# Aspen_Fever.net
KiCad netlist of a schematic drawn in EAGLE
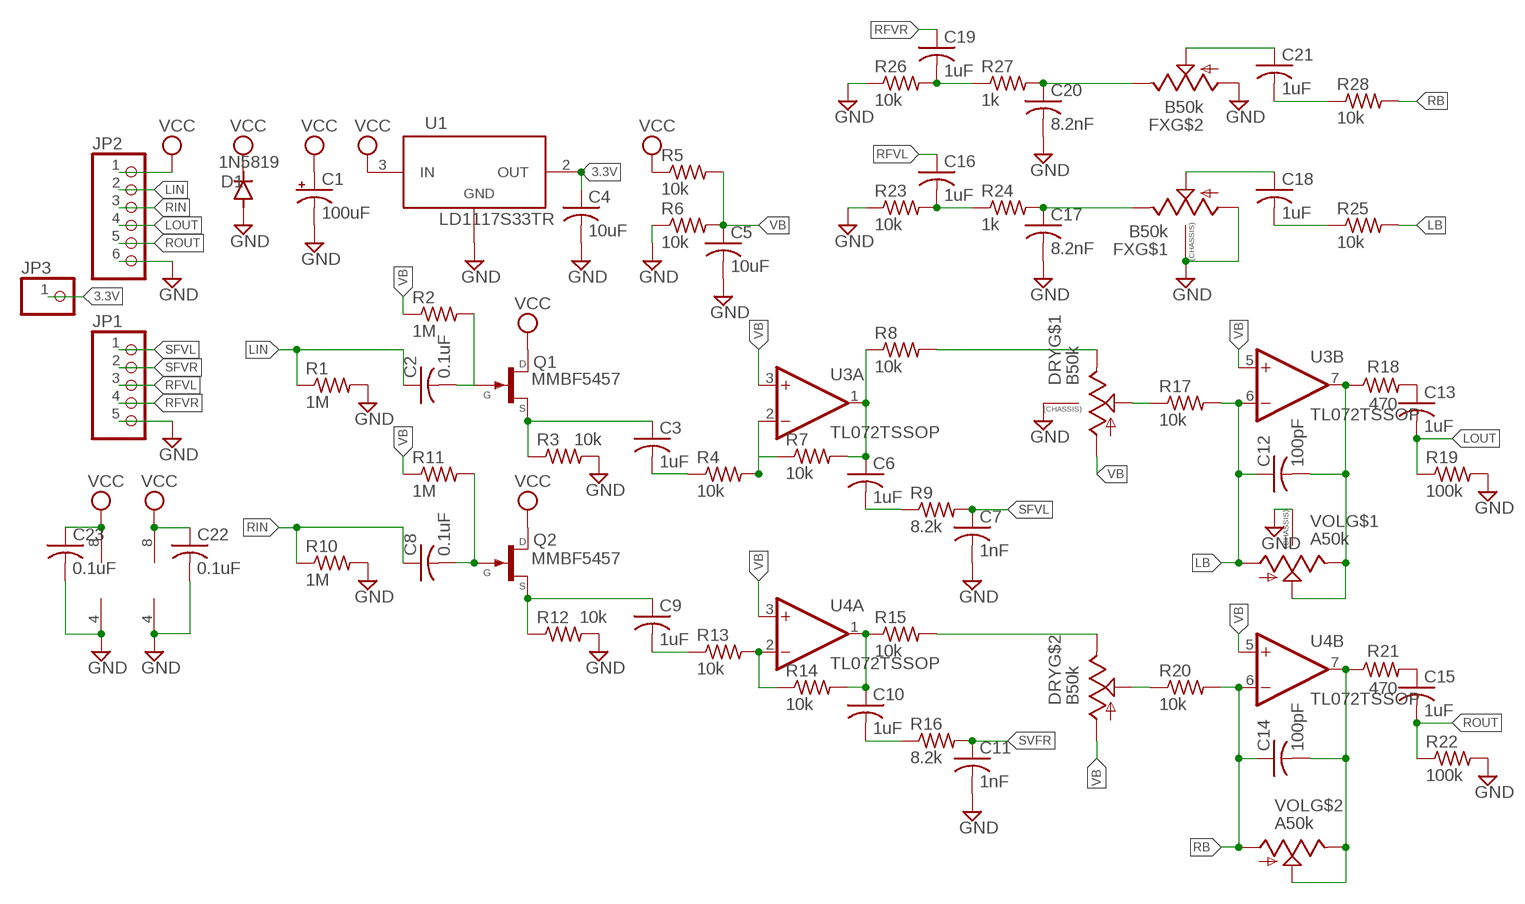
[diagram p0: schematic, sheet 1]

(export (version "E")
  (design (tool "Eeschema 10.0.6"))
  (components
    (comp (ref "C1")
      (value "100uF")
      (footprint "eagle-import:PAN_B_SMD+THRU")
      (libsource (lib "eagle-import") (part "CAP_SMD+THRUPAN_B"))
    )
    (comp (ref "C2")
      (value "0.1uF")
      (footprint "eagle-import:C0402")
      (libsource (lib "eagle-import") (part "C-USC0402"))
    )
    (comp (ref "C3")
      (value "1uF")
      (footprint "eagle-import:C0603")
      (libsource (lib "eagle-import") (part "adafruit_420_C-USC0603"))
    )
    (comp (ref "C4")
      (value "10uF")
      (footprint "eagle-import:C0805")
      (libsource (lib "eagle-import") (part "C-USC0805"))
    )
    (comp (ref "C5")
      (value "10uF")
      (footprint "eagle-import:C0805")
      (libsource (lib "eagle-import") (part "C-USC0805"))
    )
    (comp (ref "C6")
      (value "1uF")
      (footprint "eagle-import:C0603")
      (libsource (lib "eagle-import") (part "adafruit_420_C-USC0603"))
    )
    (comp (ref "C7")
      (value "1nF")
      (footprint "eagle-import:C0402")
      (libsource (lib "eagle-import") (part "C-USC0402"))
    )
    (comp (ref "C8")
      (value "0.1uF")
      (footprint "eagle-import:C0402")
      (libsource (lib "eagle-import") (part "C-USC0402"))
    )
    (comp (ref "C9")
      (value "1uF")
      (footprint "eagle-import:C0603")
      (libsource (lib "eagle-import") (part "adafruit_420_C-USC0603"))
    )
    (comp (ref "C10")
      (value "1uF")
      (footprint "eagle-import:C0603")
      (libsource (lib "eagle-import") (part "adafruit_420_C-USC0603"))
    )
    (comp (ref "C11")
      (value "1nF")
      (footprint "eagle-import:C0402")
      (libsource (lib "eagle-import") (part "C-USC0402"))
    )
    (comp (ref "C12")
      (value "100pF")
      (footprint "eagle-import:C0402")
      (libsource (lib "eagle-import") (part "C-USC0402"))
    )
    (comp (ref "C13")
      (value "1uF")
      (footprint "eagle-import:C0603")
      (libsource (lib "eagle-import") (part "adafruit_420_C-USC0603"))
    )
    (comp (ref "C14")
      (value "100pF")
      (footprint "eagle-import:C0402")
      (libsource (lib "eagle-import") (part "C-USC0402"))
    )
    (comp (ref "C15")
      (value "1uF")
      (footprint "eagle-import:C0603")
      (libsource (lib "eagle-import") (part "adafruit_420_C-USC0603"))
    )
    (comp (ref "C16")
      (value "1uF")
      (footprint "eagle-import:C0603")
      (libsource (lib "eagle-import") (part "adafruit_420_C-USC0603"))
    )
    (comp (ref "C17")
      (value "8.2nF")
      (footprint "eagle-import:C0402")
      (libsource (lib "eagle-import") (part "C-USC0402"))
    )
    (comp (ref "C18")
      (value "1uF")
      (footprint "eagle-import:C0603")
      (libsource (lib "eagle-import") (part "adafruit_420_C-USC0603"))
    )
    (comp (ref "C19")
      (value "1uF")
      (footprint "eagle-import:C0603")
      (libsource (lib "eagle-import") (part "adafruit_420_C-USC0603"))
    )
    (comp (ref "C20")
      (value "8.2nF")
      (footprint "eagle-import:C0402")
      (libsource (lib "eagle-import") (part "C-USC0402"))
    )
    (comp (ref "C21")
      (value "1uF")
      (footprint "eagle-import:C0603")
      (libsource (lib "eagle-import") (part "adafruit_420_C-USC0603"))
    )
    (comp (ref "C22")
      (value "0.1uF")
      (footprint "eagle-import:C0402")
      (libsource (lib "eagle-import") (part "C-USC0402"))
    )
    (comp (ref "C23")
      (value "0.1uF")
      (footprint "eagle-import:C0402")
      (libsource (lib "eagle-import") (part "C-USC0402"))
    )
    (comp (ref "D1")
      (value "1N5819")
      (footprint "eagle-import:SOD123")
      (libsource (lib "eagle-import") (part "DIODE-SOD123"))
    )
    (comp (ref "DRY")
      (value "B50k")
      (footprint "eagle-import:DUAL_9MM_SNAP-IN_POT")
      (libsource (lib "eagle-import") (part "ALPHA-9MM-DUALPOT"))
    )
    (comp (ref "FX")
      (value "B50k")
      (footprint "eagle-import:DUAL_9MM_SNAP-IN_POT")
      (libsource (lib "eagle-import") (part "ALPHA-9MM-DUALPOT"))
    )
    (comp (ref "JP1")
      (value "PINHD-1X5")
      (footprint "eagle-import:1X05")
      (libsource (lib "eagle-import") (part "PINHD-1X5"))
    )
    (comp (ref "JP2")
      (value "PINHD-1X6")
      (footprint "eagle-import:1X06")
      (libsource (lib "eagle-import") (part "PINHD-1X6"))
    )
    (comp (ref "JP3")
      (value "PINHD-1X1")
      (footprint "eagle-import:1X01")
      (libsource (lib "eagle-import") (part "PINHD-1X1"))
    )
    (comp (ref "Q1")
      (value "MMBF5457")
      (footprint "eagle-import:SOT23")
      (fields (field (name "MF") "ON Semiconductor"))
      (libsource (lib "eagle-import") (part "MMBF5457"))
    )
    (comp (ref "Q2")
      (value "MMBF5457")
      (footprint "eagle-import:SOT23")
      (fields (field (name "MF") "ON Semiconductor"))
      (libsource (lib "eagle-import") (part "MMBF5457"))
    )
    (comp (ref "R1")
      (value "1M")
      (footprint "eagle-import:R0402")
      (libsource (lib "eagle-import") (part "R-US_R0402"))
    )
    (comp (ref "R2")
      (value "1M")
      (footprint "eagle-import:R0402")
      (libsource (lib "eagle-import") (part "R-US_R0402"))
    )
    (comp (ref "R3")
      (value "10k")
      (footprint "eagle-import:R0402")
      (libsource (lib "eagle-import") (part "R-US_R0402"))
    )
    (comp (ref "R4")
      (value "10k")
      (footprint "eagle-import:R0402")
      (libsource (lib "eagle-import") (part "R-US_R0402"))
    )
    (comp (ref "R5")
      (value "10k")
      (footprint "eagle-import:R0402")
      (libsource (lib "eagle-import") (part "R-US_R0402"))
    )
    (comp (ref "R6")
      (value "10k")
      (footprint "eagle-import:R0402")
      (libsource (lib "eagle-import") (part "R-US_R0402"))
    )
    (comp (ref "R7")
      (value "10k")
      (footprint "eagle-import:R0402")
      (libsource (lib "eagle-import") (part "R-US_R0402"))
    )
    (comp (ref "R8")
      (value "10k")
      (footprint "eagle-import:R0402")
      (libsource (lib "eagle-import") (part "R-US_R0402"))
    )
    (comp (ref "R9")
      (value "8.2k")
      (footprint "eagle-import:R0402")
      (libsource (lib "eagle-import") (part "R-US_R0402"))
    )
    (comp (ref "R10")
      (value "1M")
      (footprint "eagle-import:R0402")
      (libsource (lib "eagle-import") (part "R-US_R0402"))
    )
    (comp (ref "R11")
      (value "1M")
      (footprint "eagle-import:R0402")
      (libsource (lib "eagle-import") (part "R-US_R0402"))
    )
    (comp (ref "R12")
      (value "10k")
      (footprint "eagle-import:R0402")
      (libsource (lib "eagle-import") (part "R-US_R0402"))
    )
    (comp (ref "R13")
      (value "10k")
      (footprint "eagle-import:R0402")
      (libsource (lib "eagle-import") (part "R-US_R0402"))
    )
    (comp (ref "R14")
      (value "10k")
      (footprint "eagle-import:R0402")
      (libsource (lib "eagle-import") (part "R-US_R0402"))
    )
    (comp (ref "R15")
      (value "10k")
      (footprint "eagle-import:R0402")
      (libsource (lib "eagle-import") (part "R-US_R0402"))
    )
    (comp (ref "R16")
      (value "8.2k")
      (footprint "eagle-import:R0402")
      (libsource (lib "eagle-import") (part "R-US_R0402"))
    )
    (comp (ref "R17")
      (value "10k")
      (footprint "eagle-import:R0402")
      (libsource (lib "eagle-import") (part "R-US_R0402"))
    )
    (comp (ref "R18")
      (value "470")
      (footprint "eagle-import:R0402")
      (libsource (lib "eagle-import") (part "R-US_R0402"))
    )
    (comp (ref "R19")
      (value "100k")
      (footprint "eagle-import:R0402")
      (libsource (lib "eagle-import") (part "R-US_R0402"))
    )
    (comp (ref "R20")
      (value "10k")
      (footprint "eagle-import:R0402")
      (libsource (lib "eagle-import") (part "R-US_R0402"))
    )
    (comp (ref "R21")
      (value "470")
      (footprint "eagle-import:R0402")
      (libsource (lib "eagle-import") (part "R-US_R0402"))
    )
    (comp (ref "R22")
      (value "100k")
      (footprint "eagle-import:R0402")
      (libsource (lib "eagle-import") (part "R-US_R0402"))
    )
    (comp (ref "R23")
      (value "10k")
      (footprint "eagle-import:R0402")
      (libsource (lib "eagle-import") (part "R-US_R0402"))
    )
    (comp (ref "R24")
      (value "1k")
      (footprint "eagle-import:R0402")
      (libsource (lib "eagle-import") (part "R-US_R0402"))
    )
    (comp (ref "R25")
      (value "10k")
      (footprint "eagle-import:R0402")
      (libsource (lib "eagle-import") (part "R-US_R0402"))
    )
    (comp (ref "R26")
      (value "10k")
      (footprint "eagle-import:R0402")
      (libsource (lib "eagle-import") (part "R-US_R0402"))
    )
    (comp (ref "R27")
      (value "1k")
      (footprint "eagle-import:R0402")
      (libsource (lib "eagle-import") (part "R-US_R0402"))
    )
    (comp (ref "R28")
      (value "10k")
      (footprint "eagle-import:R0402")
      (libsource (lib "eagle-import") (part "R-US_R0402"))
    )
    (comp (ref "U1")
      (value "LD1117S33TR")
      (footprint "eagle-import:SOT-223")
      (fields
        (field (name "DIGIKEY_PART_NUMBER") "497-1242-2-ND")
        (field (name "MANUFACTURER") "STMicroelectronics")
        (field (name "CREATED_BY") "PCBLayout.com")
      )
      (libsource (lib "eagle-import") (part "LD1117S33TR"))
    )
    (comp (ref "U3")
      (value "TL072TSSOP")
      (footprint "eagle-import:TSSOP-8")
      (libsource (lib "eagle-import") (part "TL072TSSOP"))
    )
    (comp (ref "U4")
      (value "TL072TSSOP")
      (footprint "eagle-import:TSSOP-8")
      (libsource (lib "eagle-import") (part "TL072TSSOP"))
    )
    (comp (ref "VOL")
      (value "A50k")
      (footprint "eagle-import:DUAL_9MM_SNAP-IN_POT")
      (libsource (lib "eagle-import") (part "ALPHA-9MM-DUALPOT"))
    )
  )
  (nets
    (net (code "1") (name "3.3V") (class "Default")
      (node (ref "C4") (pin "1") (pinfunction "1_1") (pintype "passive"))
      (node (ref "JP3") (pin "1") (pinfunction "1_1") (pintype "passive"))
      (node (ref "U1") (pin "2") (pinfunction "OUT_2") (pintype "output"))
      (node (ref "U1") (pin "4") (pinfunction "4_4") (pintype "passive"))
    )
    (net (code "2") (name "GND") (class "Default")
      (node (ref "C1") (pin "-") (pinfunction "-_-") (pintype "passive"))
      (node (ref "C1") (pin "--") (pinfunction "-_--") (pintype "passive"))
      (node (ref "C11") (pin "2") (pinfunction "2_2") (pintype "passive"))
      (node (ref "C17") (pin "2") (pinfunction "2_2") (pintype "passive"))
      (node (ref "C20") (pin "2") (pinfunction "2_2") (pintype "passive"))
      (node (ref "C22") (pin "2") (pinfunction "2_2") (pintype "passive"))
      (node (ref "C23") (pin "2") (pinfunction "2_2") (pintype "passive"))
      (node (ref "C4") (pin "2") (pinfunction "2_2") (pintype "passive"))
      (node (ref "C5") (pin "2") (pinfunction "2_2") (pintype "passive"))
      (node (ref "C7") (pin "2") (pinfunction "2_2") (pintype "passive"))
      (node (ref "D1") (pin "A") (pinfunction "A_A") (pintype "passive"))
      (node (ref "DRY") (pin "CHASSIS1") (pinfunction "P$1_CHASSIS1") (pintype "passive"))
      (node (ref "DRY") (pin "CHASSIS2") (pinfunction "P$1_CHASSIS2") (pintype "passive"))
      (node (ref "FX") (pin "1") (pinfunction "A_1") (pintype "passive"))
      (node (ref "FX") (pin "1B") (pinfunction "A_1B") (pintype "passive"))
      (node (ref "FX") (pin "CHASSIS1") (pinfunction "P$1_CHASSIS1") (pintype "passive"))
      (node (ref "FX") (pin "CHASSIS2") (pinfunction "P$1_CHASSIS2") (pintype "passive"))
      (node (ref "JP1") (pin "5") (pinfunction "5_5") (pintype "passive"))
      (node (ref "JP2") (pin "6") (pinfunction "6_6") (pintype "passive"))
      (node (ref "R1") (pin "2") (pinfunction "2_2") (pintype "passive"))
      (node (ref "R10") (pin "2") (pinfunction "2_2") (pintype "passive"))
      (node (ref "R12") (pin "2") (pinfunction "2_2") (pintype "passive"))
      (node (ref "R19") (pin "2") (pinfunction "2_2") (pintype "passive"))
      (node (ref "R22") (pin "2") (pinfunction "2_2") (pintype "passive"))
      (node (ref "R23") (pin "1") (pinfunction "1_1") (pintype "passive"))
      (node (ref "R26") (pin "1") (pinfunction "1_1") (pintype "passive"))
      (node (ref "R3") (pin "2") (pinfunction "2_2") (pintype "passive"))
      (node (ref "R6") (pin "1") (pinfunction "1_1") (pintype "passive"))
      (node (ref "U1") (pin "1") (pinfunction "ADJ/GND_1") (pintype "power_in"))
      (node (ref "U3") (pin "4") (pinfunction "V-_4") (pintype "power_in"))
      (node (ref "U4") (pin "4") (pinfunction "V-_4") (pintype "power_in"))
      (node (ref "VOL") (pin "CHASSIS1") (pinfunction "P$1_CHASSIS1") (pintype "passive"))
      (node (ref "VOL") (pin "CHASSIS2") (pinfunction "P$1_CHASSIS2") (pintype "passive"))
    )
    (net (code "3") (name "LB") (class "Default")
      (node (ref "C12") (pin "1") (pinfunction "1_1") (pintype "passive"))
      (node (ref "R17") (pin "2") (pinfunction "2_2") (pintype "passive"))
      (node (ref "R25") (pin "2") (pinfunction "2_2") (pintype "passive"))
      (node (ref "U3") (pin "6") (pinfunction "-IN_6") (pintype "input"))
      (node (ref "VOL") (pin "1") (pinfunction "A_1") (pintype "passive"))
    )
    (net (code "4") (name "LIN") (class "Default")
      (node (ref "C2") (pin "1") (pinfunction "1_1") (pintype "passive"))
      (node (ref "JP2") (pin "2") (pinfunction "2_2") (pintype "passive"))
      (node (ref "R1") (pin "1") (pinfunction "1_1") (pintype "passive"))
    )
    (net (code "5") (name "LOUT") (class "Default")
      (node (ref "C13") (pin "2") (pinfunction "2_2") (pintype "passive"))
      (node (ref "JP2") (pin "4") (pinfunction "4_4") (pintype "passive"))
      (node (ref "R19") (pin "1") (pinfunction "1_1") (pintype "passive"))
    )
    (net (code "6") (name "Net-(C3-Pad2)") (class "Default")
      (node (ref "C3") (pin "2") (pinfunction "2_2") (pintype "passive"))
      (node (ref "R4") (pin "1") (pinfunction "1_1") (pintype "passive"))
    )
    (net (code "7") (name "Net-(C6-Pad2)") (class "Default")
      (node (ref "C6") (pin "2") (pinfunction "2_2") (pintype "passive"))
      (node (ref "R9") (pin "1") (pinfunction "1_1") (pintype "passive"))
    )
    (net (code "8") (name "Net-(C9-Pad2)") (class "Default")
      (node (ref "C9") (pin "2") (pinfunction "2_2") (pintype "passive"))
      (node (ref "R13") (pin "1") (pinfunction "1_1") (pintype "passive"))
    )
    (net (code "9") (name "Net-(C10-Pad2)") (class "Default")
      (node (ref "C10") (pin "2") (pinfunction "2_2") (pintype "passive"))
      (node (ref "R16") (pin "1") (pinfunction "1_1") (pintype "passive"))
    )
    (net (code "10") (name "Net-(C13-Pad1)") (class "Default")
      (node (ref "C13") (pin "1") (pinfunction "1_1") (pintype "passive"))
      (node (ref "R18") (pin "2") (pinfunction "2_2") (pintype "passive"))
    )
    (net (code "11") (name "Net-(C15-Pad1)") (class "Default")
      (node (ref "C15") (pin "1") (pinfunction "1_1") (pintype "passive"))
      (node (ref "R21") (pin "2") (pinfunction "2_2") (pintype "passive"))
    )
    (net (code "12") (name "Net-(C16-Pad2)") (class "Default")
      (node (ref "C16") (pin "2") (pinfunction "2_2") (pintype "passive"))
      (node (ref "R23") (pin "2") (pinfunction "2_2") (pintype "passive"))
      (node (ref "R24") (pin "1") (pinfunction "1_1") (pintype "passive"))
    )
    (net (code "13") (name "Net-(C18-Pad2)") (class "Default")
      (node (ref "C18") (pin "2") (pinfunction "2_2") (pintype "passive"))
      (node (ref "R25") (pin "1") (pinfunction "1_1") (pintype "passive"))
    )
    (net (code "14") (name "Net-(C19-Pad2)") (class "Default")
      (node (ref "C19") (pin "2") (pinfunction "2_2") (pintype "passive"))
      (node (ref "R26") (pin "2") (pinfunction "2_2") (pintype "passive"))
      (node (ref "R27") (pin "1") (pinfunction "1_1") (pintype "passive"))
    )
    (net (code "15") (name "Net-(C21-Pad2)") (class "Default")
      (node (ref "C21") (pin "2") (pinfunction "2_2") (pintype "passive"))
      (node (ref "R28") (pin "1") (pinfunction "1_1") (pintype "passive"))
    )
    (net (code "16") (name "Net-(DRYA-E)") (class "Default")
      (node (ref "DRY") (pin "3") (pinfunction "E_3") (pintype "passive"))
      (node (ref "R8") (pin "2") (pinfunction "2_2") (pintype "passive"))
    )
    (net (code "17") (name "Net-(DRYA-S)") (class "Default")
      (node (ref "DRY") (pin "2") (pinfunction "S_2") (pintype "passive"))
      (node (ref "R17") (pin "1") (pinfunction "1_1") (pintype "passive"))
    )
    (net (code "18") (name "Net-(DRYB-E)") (class "Default")
      (node (ref "DRY") (pin "3B") (pinfunction "E_3B") (pintype "passive"))
      (node (ref "R15") (pin "2") (pinfunction "2_2") (pintype "passive"))
    )
    (net (code "19") (name "Net-(DRYB-S)") (class "Default")
      (node (ref "DRY") (pin "2B") (pinfunction "S_2B") (pintype "passive"))
      (node (ref "R20") (pin "1") (pinfunction "1_1") (pintype "passive"))
    )
    (net (code "20") (name "Net-(FXA-E)") (class "Default")
      (node (ref "C17") (pin "1") (pinfunction "1_1") (pintype "passive"))
      (node (ref "FX") (pin "3") (pinfunction "E_3") (pintype "passive"))
      (node (ref "R24") (pin "2") (pinfunction "2_2") (pintype "passive"))
    )
    (net (code "21") (name "Net-(FXA-S)") (class "Default")
      (node (ref "C18") (pin "1") (pinfunction "1_1") (pintype "passive"))
      (node (ref "FX") (pin "2") (pinfunction "S_2") (pintype "passive"))
    )
    (net (code "22") (name "Net-(FXB-E)") (class "Default")
      (node (ref "C20") (pin "1") (pinfunction "1_1") (pintype "passive"))
      (node (ref "FX") (pin "3B") (pinfunction "E_3B") (pintype "passive"))
      (node (ref "R27") (pin "2") (pinfunction "2_2") (pintype "passive"))
    )
    (net (code "23") (name "Net-(FXB-S)") (class "Default")
      (node (ref "C21") (pin "1") (pinfunction "1_1") (pintype "passive"))
      (node (ref "FX") (pin "2B") (pinfunction "S_2B") (pintype "passive"))
    )
    (net (code "24") (name "Net-(Q1-G)") (class "Default")
      (node (ref "C2") (pin "2") (pinfunction "2_2") (pintype "passive"))
      (node (ref "Q1") (pin "3") (pinfunction "G_3") (pintype "passive"))
      (node (ref "R2") (pin "2") (pinfunction "2_2") (pintype "passive"))
    )
    (net (code "25") (name "Net-(Q1-S)") (class "Default")
      (node (ref "C3") (pin "1") (pinfunction "1_1") (pintype "passive"))
      (node (ref "Q1") (pin "2") (pinfunction "S_2") (pintype "passive"))
      (node (ref "R3") (pin "1") (pinfunction "1_1") (pintype "passive"))
    )
    (net (code "26") (name "Net-(Q2-G)") (class "Default")
      (node (ref "C8") (pin "2") (pinfunction "2_2") (pintype "passive"))
      (node (ref "Q2") (pin "3") (pinfunction "G_3") (pintype "passive"))
      (node (ref "R11") (pin "2") (pinfunction "2_2") (pintype "passive"))
    )
    (net (code "27") (name "Net-(Q2-S)") (class "Default")
      (node (ref "C9") (pin "1") (pinfunction "1_1") (pintype "passive"))
      (node (ref "Q2") (pin "2") (pinfunction "S_2") (pintype "passive"))
      (node (ref "R12") (pin "1") (pinfunction "1_1") (pintype "passive"))
    )
    (net (code "28") (name "Net-(U3A--IN)") (class "Default")
      (node (ref "R4") (pin "2") (pinfunction "2_2") (pintype "passive"))
      (node (ref "R7") (pin "1") (pinfunction "1_1") (pintype "passive"))
      (node (ref "U3") (pin "2") (pinfunction "-IN_2") (pintype "input"))
    )
    (net (code "29") (name "Net-(U3A-OUT)") (class "Default")
      (node (ref "C6") (pin "1") (pinfunction "1_1") (pintype "passive"))
      (node (ref "R7") (pin "2") (pinfunction "2_2") (pintype "passive"))
      (node (ref "R8") (pin "1") (pinfunction "1_1") (pintype "passive"))
      (node (ref "U3") (pin "1") (pinfunction "OUT_1") (pintype "output"))
    )
    (net (code "30") (name "Net-(U3B-OUT)") (class "Default")
      (node (ref "C12") (pin "2") (pinfunction "2_2") (pintype "passive"))
      (node (ref "R18") (pin "1") (pinfunction "1_1") (pintype "passive"))
      (node (ref "U3") (pin "7") (pinfunction "OUT_7") (pintype "output"))
      (node (ref "VOL") (pin "2") (pinfunction "S_2") (pintype "passive"))
      (node (ref "VOL") (pin "3") (pinfunction "E_3") (pintype "passive"))
    )
    (net (code "31") (name "Net-(U4A--IN)") (class "Default")
      (node (ref "R13") (pin "2") (pinfunction "2_2") (pintype "passive"))
      (node (ref "R14") (pin "1") (pinfunction "1_1") (pintype "passive"))
      (node (ref "U4") (pin "2") (pinfunction "-IN_2") (pintype "input"))
    )
    (net (code "32") (name "Net-(U4A-OUT)") (class "Default")
      (node (ref "C10") (pin "1") (pinfunction "1_1") (pintype "passive"))
      (node (ref "R14") (pin "2") (pinfunction "2_2") (pintype "passive"))
      (node (ref "R15") (pin "1") (pinfunction "1_1") (pintype "passive"))
      (node (ref "U4") (pin "1") (pinfunction "OUT_1") (pintype "output"))
    )
    (net (code "33") (name "Net-(U4B-OUT)") (class "Default")
      (node (ref "C14") (pin "2") (pinfunction "2_2") (pintype "passive"))
      (node (ref "R21") (pin "1") (pinfunction "1_1") (pintype "passive"))
      (node (ref "U4") (pin "7") (pinfunction "OUT_7") (pintype "output"))
      (node (ref "VOL") (pin "2B") (pinfunction "S_2B") (pintype "passive"))
      (node (ref "VOL") (pin "3B") (pinfunction "E_3B") (pintype "passive"))
    )
    (net (code "34") (name "RB") (class "Default")
      (node (ref "C14") (pin "1") (pinfunction "1_1") (pintype "passive"))
      (node (ref "R20") (pin "2") (pinfunction "2_2") (pintype "passive"))
      (node (ref "R28") (pin "2") (pinfunction "2_2") (pintype "passive"))
      (node (ref "U4") (pin "6") (pinfunction "-IN_6") (pintype "input"))
      (node (ref "VOL") (pin "1B") (pinfunction "A_1B") (pintype "passive"))
    )
    (net (code "35") (name "RFVL") (class "Default")
      (node (ref "C16") (pin "1") (pinfunction "1_1") (pintype "passive"))
      (node (ref "JP1") (pin "3") (pinfunction "3_3") (pintype "passive"))
    )
    (net (code "36") (name "RFVR") (class "Default")
      (node (ref "C19") (pin "1") (pinfunction "1_1") (pintype "passive"))
      (node (ref "JP1") (pin "4") (pinfunction "4_4") (pintype "passive"))
    )
    (net (code "37") (name "RIN") (class "Default")
      (node (ref "C8") (pin "1") (pinfunction "1_1") (pintype "passive"))
      (node (ref "JP2") (pin "3") (pinfunction "3_3") (pintype "passive"))
      (node (ref "R10") (pin "1") (pinfunction "1_1") (pintype "passive"))
    )
    (net (code "38") (name "ROUT") (class "Default")
      (node (ref "C15") (pin "2") (pinfunction "2_2") (pintype "passive"))
      (node (ref "JP2") (pin "5") (pinfunction "5_5") (pintype "passive"))
      (node (ref "R22") (pin "1") (pinfunction "1_1") (pintype "passive"))
    )
    (net (code "39") (name "SFVL") (class "Default")
      (node (ref "C7") (pin "1") (pinfunction "1_1") (pintype "passive"))
      (node (ref "JP1") (pin "1") (pinfunction "1_1") (pintype "passive"))
      (node (ref "R9") (pin "2") (pinfunction "2_2") (pintype "passive"))
    )
    (net (code "40") (name "SFVR") (class "Default")
      (node (ref "JP1") (pin "2") (pinfunction "2_2") (pintype "passive"))
    )
    (net (code "41") (name "SVFR") (class "Default")
      (node (ref "C11") (pin "1") (pinfunction "1_1") (pintype "passive"))
      (node (ref "R16") (pin "2") (pinfunction "2_2") (pintype "passive"))
    )
    (net (code "42") (name "VB") (class "Default")
      (node (ref "C5") (pin "1") (pinfunction "1_1") (pintype "passive"))
      (node (ref "DRY") (pin "1") (pinfunction "A_1") (pintype "passive"))
      (node (ref "DRY") (pin "1B") (pinfunction "A_1B") (pintype "passive"))
      (node (ref "R11") (pin "1") (pinfunction "1_1") (pintype "passive"))
      (node (ref "R2") (pin "1") (pinfunction "1_1") (pintype "passive"))
      (node (ref "R5") (pin "2") (pinfunction "2_2") (pintype "passive"))
      (node (ref "R6") (pin "2") (pinfunction "2_2") (pintype "passive"))
      (node (ref "U3") (pin "3") (pinfunction "+IN_3") (pintype "input"))
      (node (ref "U3") (pin "5") (pinfunction "+IN_5") (pintype "input"))
      (node (ref "U4") (pin "3") (pinfunction "+IN_3") (pintype "input"))
      (node (ref "U4") (pin "5") (pinfunction "+IN_5") (pintype "input"))
    )
    (net (code "43") (name "VCC") (class "Default")
      (node (ref "C1") (pin "+") (pinfunction "+_+") (pintype "passive"))
      (node (ref "C1") (pin "++") (pinfunction "+_++") (pintype "passive"))
      (node (ref "C22") (pin "1") (pinfunction "1_1") (pintype "passive"))
      (node (ref "C23") (pin "1") (pinfunction "1_1") (pintype "passive"))
      (node (ref "D1") (pin "C") (pinfunction "C_C") (pintype "passive"))
      (node (ref "JP2") (pin "1") (pinfunction "1_1") (pintype "passive"))
      (node (ref "Q1") (pin "1") (pinfunction "D_1") (pintype "passive"))
      (node (ref "Q2") (pin "1") (pinfunction "D_1") (pintype "passive"))
      (node (ref "R5") (pin "1") (pinfunction "1_1") (pintype "passive"))
      (node (ref "U1") (pin "3") (pinfunction "IN_3") (pintype "input"))
      (node (ref "U3") (pin "8") (pinfunction "V+_8") (pintype "power_in"))
      (node (ref "U4") (pin "8") (pinfunction "V+_8") (pintype "power_in"))
    )
  )
)
